# Breakout_schematic.net
KiCad netlist of a schematic drawn in Altium Designer
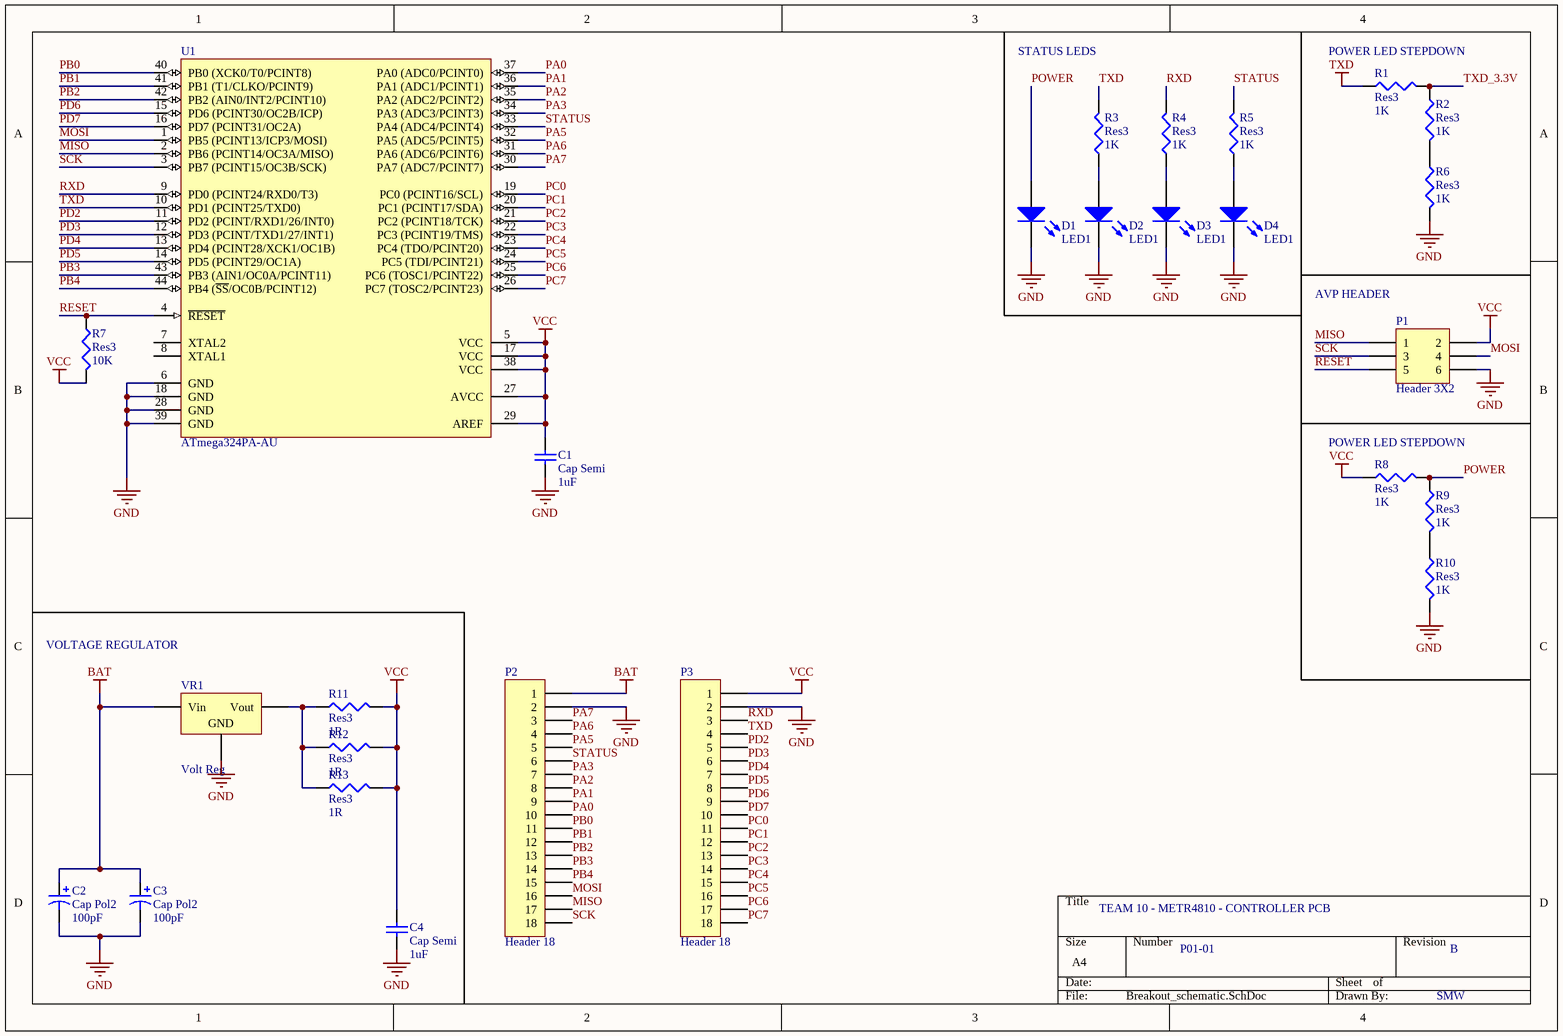
[diagram p0: Breakout_schematic.SchDoc]

(export (version "E")
  (design (tool "Eeschema 10.0.6"))
  (components
    (comp (ref "C1")
      (value "Cap Semi")
      (footprint "C1206")
      (description "Capacitor (Semiconductor SIM Model)")
      (fields (field (name "ALTIUM_VALUE") "1uF") (field (name "PUBLISHER") "Altium Limited"))
      (libsource (lib "Miscellaneous Devices") (part "Cap Semi"))
    )
    (comp (ref "C2")
      (value "Cap Pol2")
      (footprint "CAPAE9983X105M")
      (description "Polarized Capacitor (Axial)")
      (fields (field (name "ALTIUM_VALUE") "100pF") (field (name "PUBLISHER") "Altium Limited"))
      (libsource (lib "Miscellaneous Devices") (part "Cap Pol2"))
    )
    (comp (ref "C3")
      (value "Cap Pol2")
      (footprint "CAPAE9983X105M")
      (description "Polarized Capacitor (Axial)")
      (fields (field (name "ALTIUM_VALUE") "100pF") (field (name "PUBLISHER") "Altium Limited"))
      (libsource (lib "Miscellaneous Devices") (part "Cap Pol2"))
    )
    (comp (ref "C4")
      (value "Cap Semi")
      (footprint "C1206")
      (description "Capacitor (Semiconductor SIM Model)")
      (fields (field (name "ALTIUM_VALUE") "1uF") (field (name "PUBLISHER") "Altium Limited"))
      (libsource (lib "Miscellaneous Devices") (part "Cap Semi"))
    )
    (comp (ref "D1")
      (value "LED1")
      (footprint "L0603")
      (description "Typical RED GaAs LED")
      (fields (field (name "PUBLISHER") "Altium Limited"))
      (libsource (lib "Miscellaneous Devices") (part "LED1"))
    )
    (comp (ref "D2")
      (value "LED1")
      (footprint "L0603")
      (description "Typical RED GaAs LED")
      (fields (field (name "PUBLISHER") "Altium Limited"))
      (libsource (lib "Miscellaneous Devices") (part "LED1"))
    )
    (comp (ref "D3")
      (value "LED1")
      (footprint "L0603")
      (description "Typical RED GaAs LED")
      (fields (field (name "PUBLISHER") "Altium Limited"))
      (libsource (lib "Miscellaneous Devices") (part "LED1"))
    )
    (comp (ref "D4")
      (value "LED1")
      (footprint "L0603")
      (description "Typical RED GaAs LED")
      (fields (field (name "PUBLISHER") "Altium Limited"))
      (libsource (lib "Miscellaneous Devices") (part "LED1"))
    )
    (comp (ref "P1")
      (value "Header 3X2")
      (footprint "HDR2X3")
      (description "Header, 3-Pin, Dual row")
      (fields (field (name "PUBLISHER") "Altium Limited"))
      (libsource (lib "Miscellaneous Connectors") (part "Header 3X2"))
    )
    (comp (ref "P2")
      (value "Header 18")
      (footprint "HDR1X18")
      (description "Header, 18-Pin")
      (fields (field (name "PUBLISHER") "Altium Limited"))
      (libsource (lib "Miscellaneous Connectors") (part "Header 18"))
    )
    (comp (ref "P3")
      (value "Header 18")
      (footprint "HDR1X18")
      (description "Header, 18-Pin")
      (fields (field (name "PUBLISHER") "Altium Limited"))
      (libsource (lib "Miscellaneous Connectors") (part "Header 18"))
    )
    (comp (ref "R1")
      (value "Res3")
      (footprint "J1-0603")
      (description "Resistor")
      (fields (field (name "ALTIUM_VALUE") "1K") (field (name "PUBLISHER") "Altium Limited"))
      (libsource (lib "Miscellaneous Devices") (part "Res3"))
    )
    (comp (ref "R2")
      (value "Res3")
      (footprint "J1-0603")
      (description "Resistor")
      (fields (field (name "ALTIUM_VALUE") "1K") (field (name "PUBLISHER") "Altium Limited"))
      (libsource (lib "Miscellaneous Devices") (part "Res3"))
    )
    (comp (ref "R3")
      (value "Res3")
      (footprint "J1-0603")
      (description "Resistor")
      (fields (field (name "ALTIUM_VALUE") "1K") (field (name "PUBLISHER") "Altium Limited"))
      (libsource (lib "Miscellaneous Devices") (part "Res3"))
    )
    (comp (ref "R4")
      (value "Res3")
      (footprint "J1-0603")
      (description "Resistor")
      (fields (field (name "ALTIUM_VALUE") "1K") (field (name "PUBLISHER") "Altium Limited"))
      (libsource (lib "Miscellaneous Devices") (part "Res3"))
    )
    (comp (ref "R5")
      (value "Res3")
      (footprint "J1-0603")
      (description "Resistor")
      (fields (field (name "ALTIUM_VALUE") "1K") (field (name "PUBLISHER") "Altium Limited"))
      (libsource (lib "Miscellaneous Devices") (part "Res3"))
    )
    (comp (ref "R6")
      (value "Res3")
      (footprint "J1-0603")
      (description "Resistor")
      (fields (field (name "ALTIUM_VALUE") "1K") (field (name "PUBLISHER") "Altium Limited"))
      (libsource (lib "Miscellaneous Devices") (part "Res3"))
    )
    (comp (ref "R7")
      (value "Res3")
      (footprint "J1-0603")
      (description "Resistor")
      (fields (field (name "ALTIUM_VALUE") "10K") (field (name "PUBLISHER") "Altium Limited"))
      (libsource (lib "Miscellaneous Devices") (part "Res3"))
    )
    (comp (ref "R8")
      (value "Res3")
      (footprint "J1-0603")
      (description "Resistor")
      (fields (field (name "ALTIUM_VALUE") "1K") (field (name "PUBLISHER") "Altium Limited"))
      (libsource (lib "Miscellaneous Devices") (part "Res3"))
    )
    (comp (ref "R9")
      (value "Res3")
      (footprint "J1-0603")
      (description "Resistor")
      (fields (field (name "ALTIUM_VALUE") "1K") (field (name "PUBLISHER") "Altium Limited"))
      (libsource (lib "Miscellaneous Devices") (part "Res3"))
    )
    (comp (ref "R10")
      (value "Res3")
      (footprint "J1-0603")
      (description "Resistor")
      (fields (field (name "ALTIUM_VALUE") "1K") (field (name "PUBLISHER") "Altium Limited"))
      (libsource (lib "Miscellaneous Devices") (part "Res3"))
    )
    (comp (ref "R11")
      (value "Res3")
      (footprint "J1-0603")
      (description "Resistor")
      (fields (field (name "ALTIUM_VALUE") "1R") (field (name "PUBLISHER") "Altium Limited"))
      (libsource (lib "Miscellaneous Devices") (part "Res3"))
    )
    (comp (ref "R12")
      (value "Res3")
      (footprint "J1-0603")
      (description "Resistor")
      (fields (field (name "ALTIUM_VALUE") "1R") (field (name "PUBLISHER") "Altium Limited"))
      (libsource (lib "Miscellaneous Devices") (part "Res3"))
    )
    (comp (ref "R13")
      (value "Res3")
      (footprint "J1-0603")
      (description "Resistor")
      (fields (field (name "ALTIUM_VALUE") "1R") (field (name "PUBLISHER") "Altium Limited"))
      (libsource (lib "Miscellaneous Devices") (part "Res3"))
    )
    (comp (ref "U1")
      (value "ATmega324PA-AU")
      (footprint "44A_N")
      (libsource (lib "Atmel Microcontroller megaAVR") (part "ATmega324PA-AU"))
    )
    (comp (ref "VR1")
      (value "Volt Reg")
      (footprint "D2PAK_N")
      (description "Voltage Regulator")
      (fields (field (name "PUBLISHER") "Altium Limited"))
      (libsource (lib "Miscellaneous Devices") (part "Volt Reg"))
    )
  )
  (nets
    (net (code "1") (name "/MISO") (class "Default")
      (node (ref "P1") (pin "1") (pinfunction "1_1") (pintype "passive"))
      (node (ref "P2") (pin "17") (pinfunction "17_17") (pintype "passive"))
      (node (ref "U1") (pin "2") (pinfunction "PB6_(PCINT14/OC3A/MISO)_2") (pintype "bidirectional"))
    )
    (net (code "2") (name "/MOSI") (class "Default")
      (node (ref "P1") (pin "4") (pinfunction "4_4") (pintype "passive"))
      (node (ref "P2") (pin "16") (pinfunction "16_16") (pintype "passive"))
      (node (ref "U1") (pin "1") (pinfunction "PB5_(PCINT13/ICP3/MOSI)_1") (pintype "bidirectional"))
    )
    (net (code "3") (name "/PA0") (class "Default")
      (node (ref "P2") (pin "10") (pinfunction "10_10") (pintype "passive"))
      (node (ref "U1") (pin "37") (pinfunction "PA0_(ADC0/PCINT0)_37") (pintype "bidirectional"))
    )
    (net (code "4") (name "/PA1") (class "Default")
      (node (ref "P2") (pin "9") (pinfunction "9_9") (pintype "passive"))
      (node (ref "U1") (pin "36") (pinfunction "PA1_(ADC1/PCINT1)_36") (pintype "bidirectional"))
    )
    (net (code "5") (name "/PA2") (class "Default")
      (node (ref "P2") (pin "8") (pinfunction "8_8") (pintype "passive"))
      (node (ref "U1") (pin "35") (pinfunction "PA2_(ADC2/PCINT2)_35") (pintype "bidirectional"))
    )
    (net (code "6") (name "/PA3") (class "Default")
      (node (ref "P2") (pin "7") (pinfunction "7_7") (pintype "passive"))
      (node (ref "U1") (pin "34") (pinfunction "PA3_(ADC3/PCINT3)_34") (pintype "bidirectional"))
    )
    (net (code "7") (name "/PA5") (class "Default")
      (node (ref "P2") (pin "5") (pinfunction "5_5") (pintype "passive"))
      (node (ref "U1") (pin "32") (pinfunction "PA5_(ADC5/PCINT5)_32") (pintype "bidirectional"))
    )
    (net (code "8") (name "/PA6") (class "Default")
      (node (ref "P2") (pin "4") (pinfunction "4_4") (pintype "passive"))
      (node (ref "U1") (pin "31") (pinfunction "PA6_(ADC6/PCINT6)_31") (pintype "bidirectional"))
    )
    (net (code "9") (name "/PA7") (class "Default")
      (node (ref "P2") (pin "3") (pinfunction "3_3") (pintype "passive"))
      (node (ref "U1") (pin "30") (pinfunction "PA7_(ADC7/PCINT7)_30") (pintype "bidirectional"))
    )
    (net (code "10") (name "/PB0") (class "Default")
      (node (ref "P2") (pin "11") (pinfunction "11_11") (pintype "passive"))
      (node (ref "U1") (pin "40") (pinfunction "PB0_(XCK0/T0/PCINT8)_40") (pintype "bidirectional"))
    )
    (net (code "11") (name "/PB1") (class "Default")
      (node (ref "P2") (pin "12") (pinfunction "12_12") (pintype "passive"))
      (node (ref "U1") (pin "41") (pinfunction "PB1_(T1/CLKO/PCINT9)_41") (pintype "bidirectional"))
    )
    (net (code "12") (name "/PB2") (class "Default")
      (node (ref "P2") (pin "13") (pinfunction "13_13") (pintype "passive"))
      (node (ref "U1") (pin "42") (pinfunction "PB2_(AIN0/INT2/PCINT10)_42") (pintype "bidirectional"))
    )
    (net (code "13") (name "/PB3") (class "Default")
      (node (ref "P2") (pin "14") (pinfunction "14_14") (pintype "passive"))
      (node (ref "U1") (pin "43") (pinfunction "PB3_(AIN1/OC0A/PCINT11)_43") (pintype "bidirectional"))
    )
    (net (code "14") (name "/PB4") (class "Default")
      (node (ref "P2") (pin "15") (pinfunction "15_15") (pintype "passive"))
      (node (ref "U1") (pin "44") (pinfunction "PB4_(~{SS}/OC0B/PCINT12)_44") (pintype "bidirectional"))
    )
    (net (code "15") (name "/PC0") (class "Default")
      (node (ref "P3") (pin "11") (pinfunction "11_11") (pintype "passive"))
      (node (ref "U1") (pin "19") (pinfunction "PC0_(PCINT16/SCL)_19") (pintype "bidirectional"))
    )
    (net (code "16") (name "/PC1") (class "Default")
      (node (ref "P3") (pin "12") (pinfunction "12_12") (pintype "passive"))
      (node (ref "U1") (pin "20") (pinfunction "PC1_(PCINT17/SDA)_20") (pintype "bidirectional"))
    )
    (net (code "17") (name "/PC2") (class "Default")
      (node (ref "P3") (pin "13") (pinfunction "13_13") (pintype "passive"))
      (node (ref "U1") (pin "21") (pinfunction "PC2_(PCINT18/TCK)_21") (pintype "bidirectional"))
    )
    (net (code "18") (name "/PC3") (class "Default")
      (node (ref "P3") (pin "14") (pinfunction "14_14") (pintype "passive"))
      (node (ref "U1") (pin "22") (pinfunction "PC3_(PCINT19/TMS)_22") (pintype "bidirectional"))
    )
    (net (code "19") (name "/PC4") (class "Default")
      (node (ref "P3") (pin "15") (pinfunction "15_15") (pintype "passive"))
      (node (ref "U1") (pin "23") (pinfunction "PC4_(TDO/PCINT20)_23") (pintype "bidirectional"))
    )
    (net (code "20") (name "/PC5") (class "Default")
      (node (ref "P3") (pin "16") (pinfunction "16_16") (pintype "passive"))
      (node (ref "U1") (pin "24") (pinfunction "PC5_(TDI/PCINT21)_24") (pintype "bidirectional"))
    )
    (net (code "21") (name "/PC6") (class "Default")
      (node (ref "P3") (pin "17") (pinfunction "17_17") (pintype "passive"))
      (node (ref "U1") (pin "25") (pinfunction "PC6_(TOSC1/PCINT22)_25") (pintype "bidirectional"))
    )
    (net (code "22") (name "/PC7") (class "Default")
      (node (ref "P3") (pin "18") (pinfunction "18_18") (pintype "passive"))
      (node (ref "U1") (pin "26") (pinfunction "PC7_(TOSC2/PCINT23)_26") (pintype "bidirectional"))
    )
    (net (code "23") (name "/PD2") (class "Default")
      (node (ref "P3") (pin "5") (pinfunction "5_5") (pintype "passive"))
      (node (ref "U1") (pin "11") (pinfunction "PD2_(PCINT/RXD1/26/INT0)_11") (pintype "bidirectional"))
    )
    (net (code "24") (name "/PD3") (class "Default")
      (node (ref "P3") (pin "6") (pinfunction "6_6") (pintype "passive"))
      (node (ref "U1") (pin "12") (pinfunction "PD3_(PCINT/TXD1/27/INT1)_12") (pintype "bidirectional"))
    )
    (net (code "25") (name "/PD4") (class "Default")
      (node (ref "P3") (pin "7") (pinfunction "7_7") (pintype "passive"))
      (node (ref "U1") (pin "13") (pinfunction "PD4_(PCINT28/XCK1/OC1B)_13") (pintype "bidirectional"))
    )
    (net (code "26") (name "/PD5") (class "Default")
      (node (ref "P3") (pin "8") (pinfunction "8_8") (pintype "passive"))
      (node (ref "U1") (pin "14") (pinfunction "PD5_(PCINT29/OC1A)_14") (pintype "bidirectional"))
    )
    (net (code "27") (name "/PD6") (class "Default")
      (node (ref "P3") (pin "9") (pinfunction "9_9") (pintype "passive"))
      (node (ref "U1") (pin "15") (pinfunction "PD6_(PCINT30/OC2B/ICP)_15") (pintype "bidirectional"))
    )
    (net (code "28") (name "/PD7") (class "Default")
      (node (ref "P3") (pin "10") (pinfunction "10_10") (pintype "passive"))
      (node (ref "U1") (pin "16") (pinfunction "PD7_(PCINT31/OC2A)_16") (pintype "bidirectional"))
    )
    (net (code "29") (name "/POWER") (class "Default")
      (node (ref "D1") (pin "1") (pinfunction "A_1") (pintype "passive"))
      (node (ref "R8") (pin "2") (pinfunction "2_2") (pintype "passive"))
      (node (ref "R9") (pin "1") (pinfunction "1_1") (pintype "passive"))
    )
    (net (code "30") (name "/RESET") (class "Default")
      (node (ref "P1") (pin "5") (pinfunction "5_5") (pintype "passive"))
      (node (ref "R7") (pin "1") (pinfunction "1_1") (pintype "passive"))
      (node (ref "U1") (pin "4") (pinfunction "~{RESET}_4") (pintype "input"))
    )
    (net (code "31") (name "/RXD") (class "Default")
      (node (ref "P3") (pin "3") (pinfunction "3_3") (pintype "passive"))
      (node (ref "R4") (pin "2") (pinfunction "2_2") (pintype "passive"))
      (node (ref "U1") (pin "9") (pinfunction "PD0_(PCINT24/RXD0/T3)_9") (pintype "bidirectional"))
    )
    (net (code "32") (name "/SCK") (class "Default")
      (node (ref "P1") (pin "3") (pinfunction "3_3") (pintype "passive"))
      (node (ref "P2") (pin "18") (pinfunction "18_18") (pintype "passive"))
      (node (ref "U1") (pin "3") (pinfunction "PB7_(PCINT15/OC3B/SCK)_3") (pintype "bidirectional"))
    )
    (net (code "33") (name "/STATUS") (class "Default")
      (node (ref "P2") (pin "6") (pinfunction "6_6") (pintype "passive"))
      (node (ref "R5") (pin "2") (pinfunction "2_2") (pintype "passive"))
      (node (ref "U1") (pin "33") (pinfunction "PA4_(ADC4/PCINT4)_33") (pintype "bidirectional"))
    )
    (net (code "34") (name "/TXD_3.3V") (class "Default")
      (node (ref "R1") (pin "2") (pinfunction "2_2") (pintype "passive"))
      (node (ref "R2") (pin "1") (pinfunction "1_1") (pintype "passive"))
    )
    (net (code "35") (name "BAT") (class "Default")
      (node (ref "C2") (pin "1") (pinfunction "1_1") (pintype "passive"))
      (node (ref "C3") (pin "1") (pinfunction "1_1") (pintype "passive"))
      (node (ref "P2") (pin "1") (pinfunction "1_1") (pintype "passive"))
      (node (ref "VR1") (pin "1") (pinfunction "Vin_1") (pintype "passive"))
    )
    (net (code "36") (name "GND") (class "Default")
      (node (ref "C1") (pin "1") (pinfunction "1_1") (pintype "passive"))
      (node (ref "C2") (pin "2") (pinfunction "2_2") (pintype "passive"))
      (node (ref "C3") (pin "2") (pinfunction "2_2") (pintype "passive"))
      (node (ref "C4") (pin "1") (pinfunction "1_1") (pintype "passive"))
      (node (ref "D1") (pin "2") (pinfunction "K_2") (pintype "passive"))
      (node (ref "D2") (pin "2") (pinfunction "K_2") (pintype "passive"))
      (node (ref "D3") (pin "2") (pinfunction "K_2") (pintype "passive"))
      (node (ref "D4") (pin "2") (pinfunction "K_2") (pintype "passive"))
      (node (ref "P1") (pin "6") (pinfunction "6_6") (pintype "passive"))
      (node (ref "P2") (pin "2") (pinfunction "2_2") (pintype "passive"))
      (node (ref "P3") (pin "2") (pinfunction "2_2") (pintype "passive"))
      (node (ref "R10") (pin "2") (pinfunction "2_2") (pintype "passive"))
      (node (ref "R6") (pin "2") (pinfunction "2_2") (pintype "passive"))
      (node (ref "U1") (pin "18") (pinfunction "GND_18") (pintype "power_in"))
      (node (ref "U1") (pin "28") (pinfunction "GND_28") (pintype "power_in"))
      (node (ref "U1") (pin "39") (pinfunction "GND_39") (pintype "power_in"))
      (node (ref "U1") (pin "6") (pinfunction "GND_6") (pintype "power_in"))
      (node (ref "VR1") (pin "2") (pinfunction "GND_2") (pintype "passive"))
    )
    (net (code "37") (name "Net-(D2-A)") (class "Default")
      (node (ref "D2") (pin "1") (pinfunction "A_1") (pintype "passive"))
      (node (ref "R3") (pin "1") (pinfunction "1_1") (pintype "passive"))
    )
    (net (code "38") (name "Net-(D3-A)") (class "Default")
      (node (ref "D3") (pin "1") (pinfunction "A_1") (pintype "passive"))
      (node (ref "R4") (pin "1") (pinfunction "1_1") (pintype "passive"))
    )
    (net (code "39") (name "Net-(D4-A)") (class "Default")
      (node (ref "D4") (pin "1") (pinfunction "A_1") (pintype "passive"))
      (node (ref "R5") (pin "1") (pinfunction "1_1") (pintype "passive"))
    )
    (net (code "40") (name "Net-(R2-Pad2)") (class "Default")
      (node (ref "R2") (pin "2") (pinfunction "2_2") (pintype "passive"))
      (node (ref "R6") (pin "1") (pinfunction "1_1") (pintype "passive"))
    )
    (net (code "41") (name "Net-(R10-Pad1)") (class "Default")
      (node (ref "R10") (pin "1") (pinfunction "1_1") (pintype "passive"))
      (node (ref "R9") (pin "2") (pinfunction "2_2") (pintype "passive"))
    )
    (net (code "42") (name "Net-(VR1-Vout)") (class "Default")
      (node (ref "R11") (pin "1") (pinfunction "1_1") (pintype "passive"))
      (node (ref "R12") (pin "1") (pinfunction "1_1") (pintype "passive"))
      (node (ref "R13") (pin "1") (pinfunction "1_1") (pintype "passive"))
      (node (ref "VR1") (pin "3") (pinfunction "Vout_3") (pintype "passive"))
    )
    (net (code "43") (name "TXD") (class "Default")
      (node (ref "P3") (pin "4") (pinfunction "4_4") (pintype "passive"))
      (node (ref "R1") (pin "1") (pinfunction "1_1") (pintype "passive"))
      (node (ref "R3") (pin "2") (pinfunction "2_2") (pintype "passive"))
      (node (ref "U1") (pin "10") (pinfunction "PD1_(PCINT25/TXD0)_10") (pintype "bidirectional"))
    )
    (net (code "44") (name "VCC") (class "Default")
      (node (ref "C1") (pin "2") (pinfunction "2_2") (pintype "passive"))
      (node (ref "C4") (pin "2") (pinfunction "2_2") (pintype "passive"))
      (node (ref "P1") (pin "2") (pinfunction "2_2") (pintype "passive"))
      (node (ref "P3") (pin "1") (pinfunction "1_1") (pintype "passive"))
      (node (ref "R11") (pin "2") (pinfunction "2_2") (pintype "passive"))
      (node (ref "R12") (pin "2") (pinfunction "2_2") (pintype "passive"))
      (node (ref "R13") (pin "2") (pinfunction "2_2") (pintype "passive"))
      (node (ref "R7") (pin "2") (pinfunction "2_2") (pintype "passive"))
      (node (ref "R8") (pin "1") (pinfunction "1_1") (pintype "passive"))
      (node (ref "U1") (pin "17") (pinfunction "VCC_17") (pintype "power_in"))
      (node (ref "U1") (pin "27") (pinfunction "AVCC_27") (pintype "power_in"))
      (node (ref "U1") (pin "29") (pinfunction "AREF_29") (pintype "power_in"))
      (node (ref "U1") (pin "38") (pinfunction "VCC_38") (pintype "power_in"))
      (node (ref "U1") (pin "5") (pinfunction "VCC_5") (pintype "power_in"))
    )
    (net (code "45") (name "unconnected-(U1-XTAL1-Pad8)") (class "Default")
      (node (ref "U1") (pin "8") (pinfunction "XTAL1_8") (pintype "passive"))
    )
    (net (code "46") (name "unconnected-(U1-XTAL2-Pad7)") (class "Default")
      (node (ref "U1") (pin "7") (pinfunction "XTAL2_7") (pintype "passive"))
    )
  )
)
